# Sheet1.net
KiCad netlist of a schematic drawn in Altium Designer
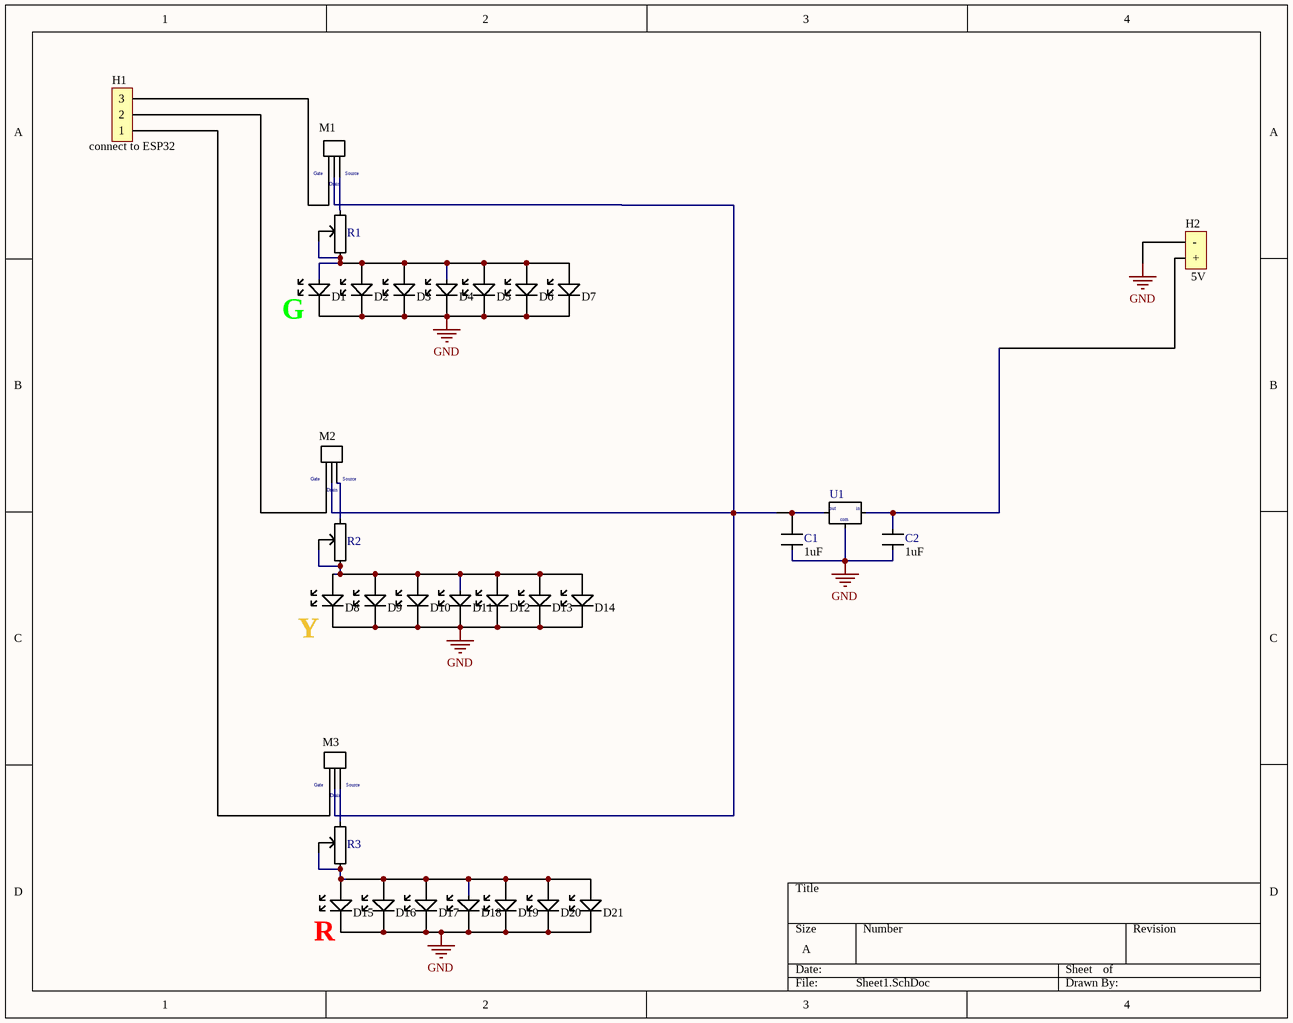
[diagram p0: Sheet1.SchDoc]

(export (version "E")
  (design (tool "Eeschema 10.0.6"))
  (components
    (comp (ref "C1")
      (value "Capacitor")
      (footprint "Capacitor")
      (fields (field (name "PARAMETER 1") "1uF"))
      (libsource (lib "Schlib1") (part "Capacitor"))
    )
    (comp (ref "C2")
      (value "Capacitor")
      (footprint "Capacitor")
      (fields (field (name "PARAMETER 1") "1uF"))
      (libsource (lib "Schlib1") (part "Capacitor"))
    )
    (comp (ref "D1") (value "LED") (footprint "LED") (libsource (lib "Schlib1") (part "LED")))
    (comp (ref "D2") (value "LED") (footprint "LED") (libsource (lib "Schlib1") (part "LED")))
    (comp (ref "D3") (value "LED") (footprint "LED") (libsource (lib "Schlib1") (part "LED")))
    (comp (ref "D4") (value "LED") (footprint "LED") (libsource (lib "Schlib1") (part "LED")))
    (comp (ref "D5") (value "LED") (footprint "LED") (libsource (lib "Schlib1") (part "LED")))
    (comp (ref "D6") (value "LED") (footprint "LED") (libsource (lib "Schlib1") (part "LED")))
    (comp (ref "D7") (value "LED") (footprint "LED") (libsource (lib "Schlib1") (part "LED")))
    (comp (ref "D8") (value "LED") (footprint "LED") (libsource (lib "Schlib1") (part "LED")))
    (comp (ref "D9") (value "LED") (footprint "LED") (libsource (lib "Schlib1") (part "LED")))
    (comp (ref "D10") (value "LED") (footprint "LED") (libsource (lib "Schlib1") (part "LED")))
    (comp (ref "D11") (value "LED") (footprint "LED") (libsource (lib "Schlib1") (part "LED")))
    (comp (ref "D12") (value "LED") (footprint "LED") (libsource (lib "Schlib1") (part "LED")))
    (comp (ref "D13") (value "LED") (footprint "LED") (libsource (lib "Schlib1") (part "LED")))
    (comp (ref "D14") (value "LED") (footprint "LED") (libsource (lib "Schlib1") (part "LED")))
    (comp (ref "D15") (value "LED") (footprint "LED") (libsource (lib "Schlib1") (part "LED")))
    (comp (ref "D16") (value "LED") (footprint "LED") (libsource (lib "Schlib1") (part "LED")))
    (comp (ref "D17") (value "LED") (footprint "LED") (libsource (lib "Schlib1") (part "LED")))
    (comp (ref "D18") (value "LED") (footprint "LED") (libsource (lib "Schlib1") (part "LED")))
    (comp (ref "D19") (value "LED") (footprint "LED") (libsource (lib "Schlib1") (part "LED")))
    (comp (ref "D20") (value "LED") (footprint "LED") (libsource (lib "Schlib1") (part "LED")))
    (comp (ref "D21") (value "LED") (footprint "LED") (libsource (lib "Schlib1") (part "LED")))
    (comp (ref "H1")
      (value "PinHeader3")
      (footprint "Header x3")
      (libsource (lib "Schlib1") (part "PinHeader3"))
    )
    (comp (ref "H2")
      (value "PinHeader2")
      (footprint "Header x2")
      (libsource (lib "Schlib1") (part "PinHeader2"))
    )
    (comp (ref "M1") (value "Mosfet") (footprint "Mosfet") (libsource (lib "Schlib1") (part "Mosfet")))
    (comp (ref "M2") (value "Mosfet") (footprint "Mosfet") (libsource (lib "Schlib1") (part "Mosfet")))
    (comp (ref "M3") (value "Mosfet") (footprint "Mosfet") (libsource (lib "Schlib1") (part "Mosfet")))
    (comp (ref "R1")
      (value "Potetiometer")
      (footprint "Potentiometer")
      (libsource (lib "Schlib1") (part "Potetiometer"))
    )
    (comp (ref "R2")
      (value "Potetiometer")
      (footprint "Potentiometer")
      (libsource (lib "Schlib1") (part "Potetiometer"))
    )
    (comp (ref "R3")
      (value "Potetiometer")
      (footprint "Potentiometer")
      (libsource (lib "Schlib1") (part "Potetiometer"))
    )
    (comp (ref "U1") (value "Regulator") (footprint "SOT-223") (libsource (lib "Schlib1") (part "Regulator")))
  )
  (nets
    (net (code "1") (name "GND") (class "Default")
      (node (ref "C1") (pin "1") (pinfunction "1_1") (pintype "passive"))
      (node (ref "C2") (pin "1") (pinfunction "1_1") (pintype "passive"))
      (node (ref "D1") (pin "1") (pinfunction "1_1") (pintype "passive"))
      (node (ref "D10") (pin "1") (pinfunction "1_1") (pintype "passive"))
      (node (ref "D11") (pin "1") (pinfunction "1_1") (pintype "passive"))
      (node (ref "D12") (pin "1") (pinfunction "1_1") (pintype "passive"))
      (node (ref "D13") (pin "1") (pinfunction "1_1") (pintype "passive"))
      (node (ref "D14") (pin "1") (pinfunction "1_1") (pintype "passive"))
      (node (ref "D15") (pin "1") (pinfunction "1_1") (pintype "passive"))
      (node (ref "D16") (pin "1") (pinfunction "1_1") (pintype "passive"))
      (node (ref "D17") (pin "1") (pinfunction "1_1") (pintype "passive"))
      (node (ref "D18") (pin "1") (pinfunction "1_1") (pintype "passive"))
      (node (ref "D19") (pin "1") (pinfunction "1_1") (pintype "passive"))
      (node (ref "D2") (pin "1") (pinfunction "1_1") (pintype "passive"))
      (node (ref "D20") (pin "1") (pinfunction "1_1") (pintype "passive"))
      (node (ref "D21") (pin "1") (pinfunction "1_1") (pintype "passive"))
      (node (ref "D3") (pin "1") (pinfunction "1_1") (pintype "passive"))
      (node (ref "D4") (pin "1") (pinfunction "1_1") (pintype "passive"))
      (node (ref "D5") (pin "1") (pinfunction "1_1") (pintype "passive"))
      (node (ref "D6") (pin "1") (pinfunction "1_1") (pintype "passive"))
      (node (ref "D7") (pin "1") (pinfunction "1_1") (pintype "passive"))
      (node (ref "D8") (pin "1") (pinfunction "1_1") (pintype "passive"))
      (node (ref "D9") (pin "1") (pinfunction "1_1") (pintype "passive"))
      (node (ref "H2") (pin "1") (pinfunction "-_1") (pintype "passive"))
      (node (ref "U1") (pin "3") (pinfunction "3_3") (pintype "passive"))
    )
    (net (code "2") (name "Net-(C1-Pad2)") (class "Default")
      (node (ref "C1") (pin "2") (pinfunction "2_2") (pintype "passive"))
      (node (ref "M1") (pin "2") (pinfunction "2_2") (pintype "passive"))
      (node (ref "M2") (pin "2") (pinfunction "2_2") (pintype "passive"))
      (node (ref "M3") (pin "2") (pinfunction "2_2") (pintype "passive"))
      (node (ref "U1") (pin "1") (pinfunction "1_1") (pintype "passive"))
    )
    (net (code "3") (name "Net-(D1-Pad2)") (class "Default")
      (node (ref "D1") (pin "2") (pinfunction "2_2") (pintype "passive"))
      (node (ref "D2") (pin "2") (pinfunction "2_2") (pintype "passive"))
      (node (ref "D3") (pin "2") (pinfunction "2_2") (pintype "passive"))
      (node (ref "D4") (pin "2") (pinfunction "2_2") (pintype "passive"))
      (node (ref "D5") (pin "2") (pinfunction "2_2") (pintype "passive"))
      (node (ref "D6") (pin "2") (pinfunction "2_2") (pintype "passive"))
      (node (ref "D7") (pin "2") (pinfunction "2_2") (pintype "passive"))
      (node (ref "R1") (pin "1") (pinfunction "1_1") (pintype "passive"))
      (node (ref "R1") (pin "3") (pinfunction "3_3") (pintype "passive"))
    )
    (net (code "4") (name "Net-(D10-Pad2)") (class "Default")
      (node (ref "D10") (pin "2") (pinfunction "2_2") (pintype "passive"))
      (node (ref "D11") (pin "2") (pinfunction "2_2") (pintype "passive"))
      (node (ref "D12") (pin "2") (pinfunction "2_2") (pintype "passive"))
      (node (ref "D13") (pin "2") (pinfunction "2_2") (pintype "passive"))
      (node (ref "D14") (pin "2") (pinfunction "2_2") (pintype "passive"))
      (node (ref "D8") (pin "2") (pinfunction "2_2") (pintype "passive"))
      (node (ref "D9") (pin "2") (pinfunction "2_2") (pintype "passive"))
      (node (ref "R2") (pin "1") (pinfunction "1_1") (pintype "passive"))
      (node (ref "R2") (pin "3") (pinfunction "3_3") (pintype "passive"))
    )
    (net (code "5") (name "Net-(D15-Pad2)") (class "Default")
      (node (ref "D15") (pin "2") (pinfunction "2_2") (pintype "passive"))
      (node (ref "D16") (pin "2") (pinfunction "2_2") (pintype "passive"))
      (node (ref "D17") (pin "2") (pinfunction "2_2") (pintype "passive"))
      (node (ref "D18") (pin "2") (pinfunction "2_2") (pintype "passive"))
      (node (ref "D19") (pin "2") (pinfunction "2_2") (pintype "passive"))
      (node (ref "D20") (pin "2") (pinfunction "2_2") (pintype "passive"))
      (node (ref "D21") (pin "2") (pinfunction "2_2") (pintype "passive"))
      (node (ref "R3") (pin "1") (pinfunction "1_1") (pintype "passive"))
      (node (ref "R3") (pin "3") (pinfunction "3_3") (pintype "passive"))
    )
    (net (code "6") (name "Net-(H1-Pad1)") (class "Default")
      (node (ref "H1") (pin "1") (pinfunction "1_1") (pintype "passive"))
      (node (ref "M3") (pin "1") (pinfunction "1_1") (pintype "passive"))
    )
    (net (code "7") (name "Net-(H1-Pad2)") (class "Default")
      (node (ref "H1") (pin "2") (pinfunction "2_2") (pintype "passive"))
      (node (ref "M2") (pin "1") (pinfunction "1_1") (pintype "passive"))
    )
    (net (code "8") (name "Net-(H1-Pad3)") (class "Default")
      (node (ref "H1") (pin "3") (pinfunction "3_3") (pintype "passive"))
      (node (ref "M1") (pin "1") (pinfunction "1_1") (pintype "passive"))
    )
    (net (code "9") (name "Net-(H2-+)") (class "Default")
      (node (ref "C2") (pin "2") (pinfunction "2_2") (pintype "passive"))
      (node (ref "H2") (pin "2") (pinfunction "+_2") (pintype "passive"))
      (node (ref "U1") (pin "2") (pinfunction "2_2") (pintype "passive"))
    )
    (net (code "10") (name "Net-(M1-Pad3)") (class "Default")
      (node (ref "M1") (pin "3") (pinfunction "3_3") (pintype "passive"))
      (node (ref "R1") (pin "2") (pinfunction "2_2") (pintype "passive"))
    )
    (net (code "11") (name "Net-(M2-Pad3)") (class "Default")
      (node (ref "M2") (pin "3") (pinfunction "3_3") (pintype "passive"))
      (node (ref "R2") (pin "2") (pinfunction "2_2") (pintype "passive"))
    )
    (net (code "12") (name "Net-(M3-Pad3)") (class "Default")
      (node (ref "M3") (pin "3") (pinfunction "3_3") (pintype "passive"))
      (node (ref "R3") (pin "2") (pinfunction "2_2") (pintype "passive"))
    )
  )
)
